# OLED.net
KiCad netlist of a schematic drawn in Altium Designer
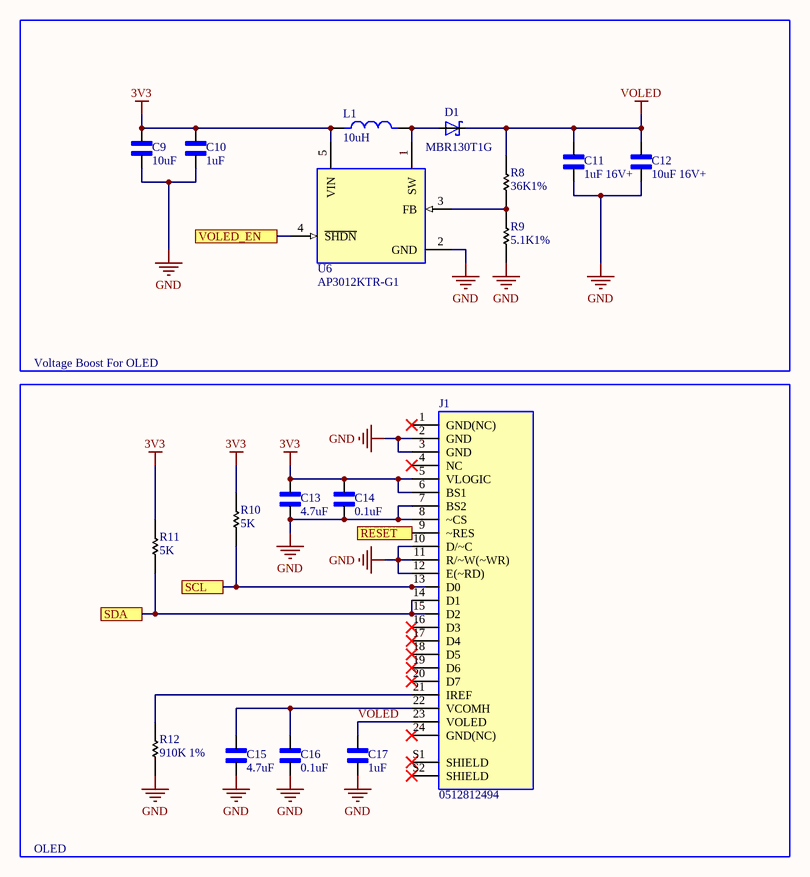
[diagram p0: OLED.SchDoc]

(export (version "E")
  (design (tool "Eeschema 10.0.6"))
  (components
    (comp (ref "C9")
      (value "10uF")
      (footprint "CHIP_0603")
      (description "Generic 0603 Ceramic Capacitor")
      (fields (field (name "MP") "AC0402FR-071ML") (field (name "MF") "Yageo"))
      (libsource (lib "Guitar_Multi_Effect_Interface_lib") (part "0603 Ceramic Capacitor"))
    )
    (comp (ref "C10")
      (value "1uF")
      (footprint "CHIP_0603")
      (description "Generic 0603 Ceramic Capacitor")
      (fields (field (name "MP") "AC0402FR-071ML") (field (name "MF") "Yageo"))
      (libsource (lib "Guitar_Multi_Effect_Interface_lib") (part "0603 Ceramic Capacitor"))
    )
    (comp (ref "C11")
      (value "1uF 16V+")
      (footprint "CHIP_0603")
      (description "Generic 0603 Ceramic Capacitor")
      (fields (field (name "MP") "AC0402FR-071ML") (field (name "MF") "Yageo"))
      (libsource (lib "Guitar_Multi_Effect_Interface_lib") (part "0603 Ceramic Capacitor"))
    )
    (comp (ref "C12")
      (value "10uF 16V+")
      (footprint "CHIP_0603")
      (description "Generic 0603 Ceramic Capacitor")
      (fields (field (name "MP") "AC0402FR-071ML") (field (name "MF") "Yageo"))
      (libsource (lib "Guitar_Multi_Effect_Interface_lib") (part "0603 Ceramic Capacitor"))
    )
    (comp (ref "C13")
      (value "4.7uF")
      (footprint "CHIP_0603")
      (description "Generic 0603 Ceramic Capacitor")
      (fields (field (name "MP") "AC0402FR-071ML") (field (name "MF") "Yageo"))
      (libsource (lib "Guitar_Multi_Effect_Interface_lib") (part "0603 Ceramic Capacitor"))
    )
    (comp (ref "C14")
      (value "0.1uF")
      (footprint "CHIP_0603")
      (description "Generic 0603 Ceramic Capacitor")
      (fields (field (name "MP") "AC0402FR-071ML") (field (name "MF") "Yageo"))
      (libsource (lib "Guitar_Multi_Effect_Interface_lib") (part "0603 Ceramic Capacitor"))
    )
    (comp (ref "C15")
      (value "4.7uF")
      (footprint "CHIP_0603")
      (description "Generic 0603 Ceramic Capacitor")
      (fields (field (name "MP") "AC0402FR-071ML") (field (name "MF") "Yageo"))
      (libsource (lib "Guitar_Multi_Effect_Interface_lib") (part "0603 Ceramic Capacitor"))
    )
    (comp (ref "C16")
      (value "0.1uF")
      (footprint "CHIP_0603")
      (description "Generic 0603 Ceramic Capacitor")
      (fields (field (name "MP") "AC0402FR-071ML") (field (name "MF") "Yageo"))
      (libsource (lib "Guitar_Multi_Effect_Interface_lib") (part "0603 Ceramic Capacitor"))
    )
    (comp (ref "C17")
      (value "1uF")
      (footprint "CHIP_0603")
      (description "Generic 0603 Ceramic Capacitor")
      (fields (field (name "MP") "AC0402FR-071ML") (field (name "MF") "Yageo"))
      (libsource (lib "Guitar_Multi_Effect_Interface_lib") (part "0603 Ceramic Capacitor"))
    )
    (comp (ref "D1")
      (value "MBR130T1G")
      (footprint "Multi_Effect_Interface_lib:SOD-123-2")
      (description "Diode Schottky 30 V 1A Surface Mount SOD-123")
      (fields (field (name "MP") "MBR0530") (field (name "MF") "ON Semiconductor"))
      (libsource (lib "Guitar_Multi_Effect_Interface_lib") (part "MBR130T1G"))
    )
    (comp (ref "J1")
      (value "0512812494")
      (footprint "Multi_Effect_Interface_lib:Top_Connector_Config_0512812494")
      (fields (field (name "MP") "2-84952-4") (field (name "MF") "TE Connectivity"))
      (libsource (lib "Guitar_Multi_Effect_Interface_lib") (part "0512812494"))
    )
    (comp (ref "L1")
      (value "10uH")
      (footprint "Multi_Effect_Interface_lib:IND_LQH3NPZ100MMEL")
      (description "Inductor with Inductance: 10uH Tol. +/-20%, Package: 1212 _3030_")
      (fields (field (name "MP") "LQH3NPZ100MMEL") (field (name "DIGI-KEY_PART_NUMBER") "490-15968-1-ND"))
      (libsource (lib "Guitar_Multi_Effect_Interface_lib") (part "LQH3NPZ100MMEL"))
    )
    (comp (ref "R8")
      (value "36K1%")
      (footprint "CHIP_R_0603")
      (description "Generic 0603 Resistor")
      (libsource (lib "Guitar_Multi_Effect_Interface_lib") (part "0603 Generic Resistor"))
    )
    (comp (ref "R9")
      (value "5.1K1%")
      (footprint "CHIP_R_0603")
      (description "Generic 0603 Resistor")
      (libsource (lib "Guitar_Multi_Effect_Interface_lib") (part "0603 Generic Resistor"))
    )
    (comp (ref "R10")
      (value "5K")
      (footprint "CHIP_R_0603")
      (description "Generic 0603 Resistor")
      (libsource (lib "Guitar_Multi_Effect_Interface_lib") (part "0603 Generic Resistor"))
    )
    (comp (ref "R11")
      (value "5K")
      (footprint "CHIP_R_0603")
      (description "Generic 0603 Resistor")
      (libsource (lib "Guitar_Multi_Effect_Interface_lib") (part "0603 Generic Resistor"))
    )
    (comp (ref "R12")
      (value "910K 1%")
      (footprint "CHIP_R_0603")
      (description "Generic 0603 Resistor")
      (libsource (lib "Guitar_Multi_Effect_Interface_lib") (part "0603 Generic Resistor"))
    )
    (comp (ref "U6")
      (value "AP3012KTR-G1")
      (footprint "Multi_Effect_Interface_lib:SOT-23")
      (description "Boost Switching Regulator IC Positive Adjustable 1.25V 1 Output 500mA _Switch_ SC-74A, SOT-753")
      (fields (field (name "MF") "Diodes Inc."))
      (libsource (lib "Guitar_Multi_Effect_Interface_lib") (part "AP3012KTR-G1"))
    )
  )
  (nets
    (net (code "1") (name "/RESET") (class "Default")
      (node (ref "J1") (pin "9") (pinfunction "~RES_9") (pintype "passive"))
    )
    (net (code "2") (name "/SCL") (class "Default")
      (node (ref "J1") (pin "13") (pinfunction "D0_13") (pintype "passive"))
      (node (ref "R10") (pin "2") (pinfunction "2_2") (pintype "passive"))
    )
    (net (code "3") (name "/SDA") (class "Default")
      (node (ref "J1") (pin "14") (pinfunction "D1_14") (pintype "passive"))
      (node (ref "J1") (pin "15") (pinfunction "D2_15") (pintype "passive"))
      (node (ref "R11") (pin "2") (pinfunction "2_2") (pintype "passive"))
    )
    (net (code "4") (name "/VOLED_EN") (class "Default")
      (node (ref "U6") (pin "4") (pinfunction "~{SHDN}_4") (pintype "input"))
    )
    (net (code "5") (name "3V3") (class "Default")
      (node (ref "C10") (pin "1") (pinfunction "1_1") (pintype "passive"))
      (node (ref "C13") (pin "1") (pinfunction "1_1") (pintype "passive"))
      (node (ref "C14") (pin "1") (pinfunction "1_1") (pintype "passive"))
      (node (ref "C9") (pin "1") (pinfunction "1_1") (pintype "passive"))
      (node (ref "J1") (pin "5") (pinfunction "VLOGIC_5") (pintype "passive"))
      (node (ref "J1") (pin "6") (pinfunction "BS1_6") (pintype "passive"))
      (node (ref "L1") (pin "1") (pinfunction "1_1") (pintype "passive"))
      (node (ref "R10") (pin "1") (pinfunction "1_1") (pintype "passive"))
      (node (ref "R11") (pin "1") (pinfunction "1_1") (pintype "passive"))
      (node (ref "U6") (pin "5") (pinfunction "VIN_5") (pintype "power_in"))
    )
    (net (code "6") (name "GND") (class "Default")
      (node (ref "C10") (pin "2") (pinfunction "2_2") (pintype "passive"))
      (node (ref "C11") (pin "2") (pinfunction "2_2") (pintype "passive"))
      (node (ref "C12") (pin "2") (pinfunction "2_2") (pintype "passive"))
      (node (ref "C13") (pin "2") (pinfunction "2_2") (pintype "passive"))
      (node (ref "C14") (pin "2") (pinfunction "2_2") (pintype "passive"))
      (node (ref "C15") (pin "2") (pinfunction "2_2") (pintype "passive"))
      (node (ref "C16") (pin "2") (pinfunction "2_2") (pintype "passive"))
      (node (ref "C17") (pin "2") (pinfunction "2_2") (pintype "passive"))
      (node (ref "C9") (pin "2") (pinfunction "2_2") (pintype "passive"))
      (node (ref "J1") (pin "10") (pinfunction "D/~C_10") (pintype "passive"))
      (node (ref "J1") (pin "11") (pinfunction "R/~W(~WR)_11") (pintype "passive"))
      (node (ref "J1") (pin "12") (pinfunction "E(~RD)_12") (pintype "passive"))
      (node (ref "J1") (pin "2") (pinfunction "GND_2") (pintype "passive"))
      (node (ref "J1") (pin "3") (pinfunction "GND_3") (pintype "passive"))
      (node (ref "J1") (pin "7") (pinfunction "BS2_7") (pintype "passive"))
      (node (ref "J1") (pin "8") (pinfunction "~CS_8") (pintype "passive"))
      (node (ref "R12") (pin "2") (pinfunction "2_2") (pintype "passive"))
      (node (ref "R9") (pin "2") (pinfunction "2_2") (pintype "passive"))
      (node (ref "U6") (pin "2") (pinfunction "GND_2") (pintype "power_in"))
    )
    (net (code "7") (name "Net-(J1-IREF)") (class "Default")
      (node (ref "J1") (pin "21") (pinfunction "IREF_21") (pintype "passive"))
      (node (ref "R12") (pin "1") (pinfunction "1_1") (pintype "passive"))
    )
    (net (code "8") (name "Net-(J1-VCOMH)") (class "Default")
      (node (ref "C15") (pin "1") (pinfunction "1_1") (pintype "passive"))
      (node (ref "C16") (pin "1") (pinfunction "1_1") (pintype "passive"))
      (node (ref "J1") (pin "22") (pinfunction "VCOMH_22") (pintype "passive"))
    )
    (net (code "9") (name "Net-(U6-FB)") (class "Default")
      (node (ref "R8") (pin "2") (pinfunction "2_2") (pintype "passive"))
      (node (ref "R9") (pin "1") (pinfunction "1_1") (pintype "passive"))
      (node (ref "U6") (pin "3") (pinfunction "FB_3") (pintype "input"))
    )
    (net (code "10") (name "Net-(U6-SW)") (class "Default")
      (node (ref "D1") (pin "A") (pinfunction "A_A") (pintype "passive"))
      (node (ref "L1") (pin "2") (pinfunction "2_2") (pintype "passive"))
      (node (ref "U6") (pin "1") (pinfunction "SW_1") (pintype "passive"))
    )
    (net (code "11") (name "VOLED") (class "Default")
      (node (ref "C11") (pin "1") (pinfunction "1_1") (pintype "passive"))
      (node (ref "C12") (pin "1") (pinfunction "1_1") (pintype "passive"))
      (node (ref "C17") (pin "1") (pinfunction "1_1") (pintype "passive"))
      (node (ref "D1") (pin "C") (pinfunction "C_C") (pintype "passive"))
      (node (ref "J1") (pin "23") (pinfunction "VOLED_23") (pintype "passive"))
      (node (ref "R8") (pin "1") (pinfunction "1_1") (pintype "passive"))
    )
    (net (code "12") (name "unconnected-(J1-D3-Pad16)") (class "Default")
      (node (ref "J1") (pin "16") (pinfunction "D3_16") (pintype "passive+no_connect"))
    )
    (net (code "13") (name "unconnected-(J1-D4-Pad17)") (class "Default")
      (node (ref "J1") (pin "17") (pinfunction "D4_17") (pintype "passive+no_connect"))
    )
    (net (code "14") (name "unconnected-(J1-D5-Pad18)") (class "Default")
      (node (ref "J1") (pin "18") (pinfunction "D5_18") (pintype "passive+no_connect"))
    )
    (net (code "15") (name "unconnected-(J1-D6-Pad19)") (class "Default")
      (node (ref "J1") (pin "19") (pinfunction "D6_19") (pintype "passive+no_connect"))
    )
    (net (code "16") (name "unconnected-(J1-D7-Pad20)") (class "Default")
      (node (ref "J1") (pin "20") (pinfunction "D7_20") (pintype "passive+no_connect"))
    )
    (net (code "17") (name "unconnected-(J1-GND(NC)-Pad1)") (class "Default")
      (node (ref "J1") (pin "1") (pinfunction "GND(NC)_1") (pintype "passive+no_connect"))
    )
    (net (code "18") (name "unconnected-(J1-GND(NC)-Pad24)") (class "Default")
      (node (ref "J1") (pin "24") (pinfunction "GND(NC)_24") (pintype "passive+no_connect"))
    )
    (net (code "19") (name "unconnected-(J1-NC-Pad4)") (class "Default")
      (node (ref "J1") (pin "4") (pinfunction "NC_4") (pintype "passive+no_connect"))
    )
    (net (code "20") (name "unconnected-(J1-SHIELD-PadS1)") (class "Default")
      (node (ref "J1") (pin "S1") (pinfunction "SHIELD_S1") (pintype "passive+no_connect"))
    )
    (net (code "21") (name "unconnected-(J1-SHIELD-PadS2)") (class "Default")
      (node (ref "J1") (pin "S2") (pinfunction "SHIELD_S2") (pintype "passive+no_connect"))
    )
  )
)
